# fpga_headers.net
KiCad netlist of a schematic drawn in Altium Designer
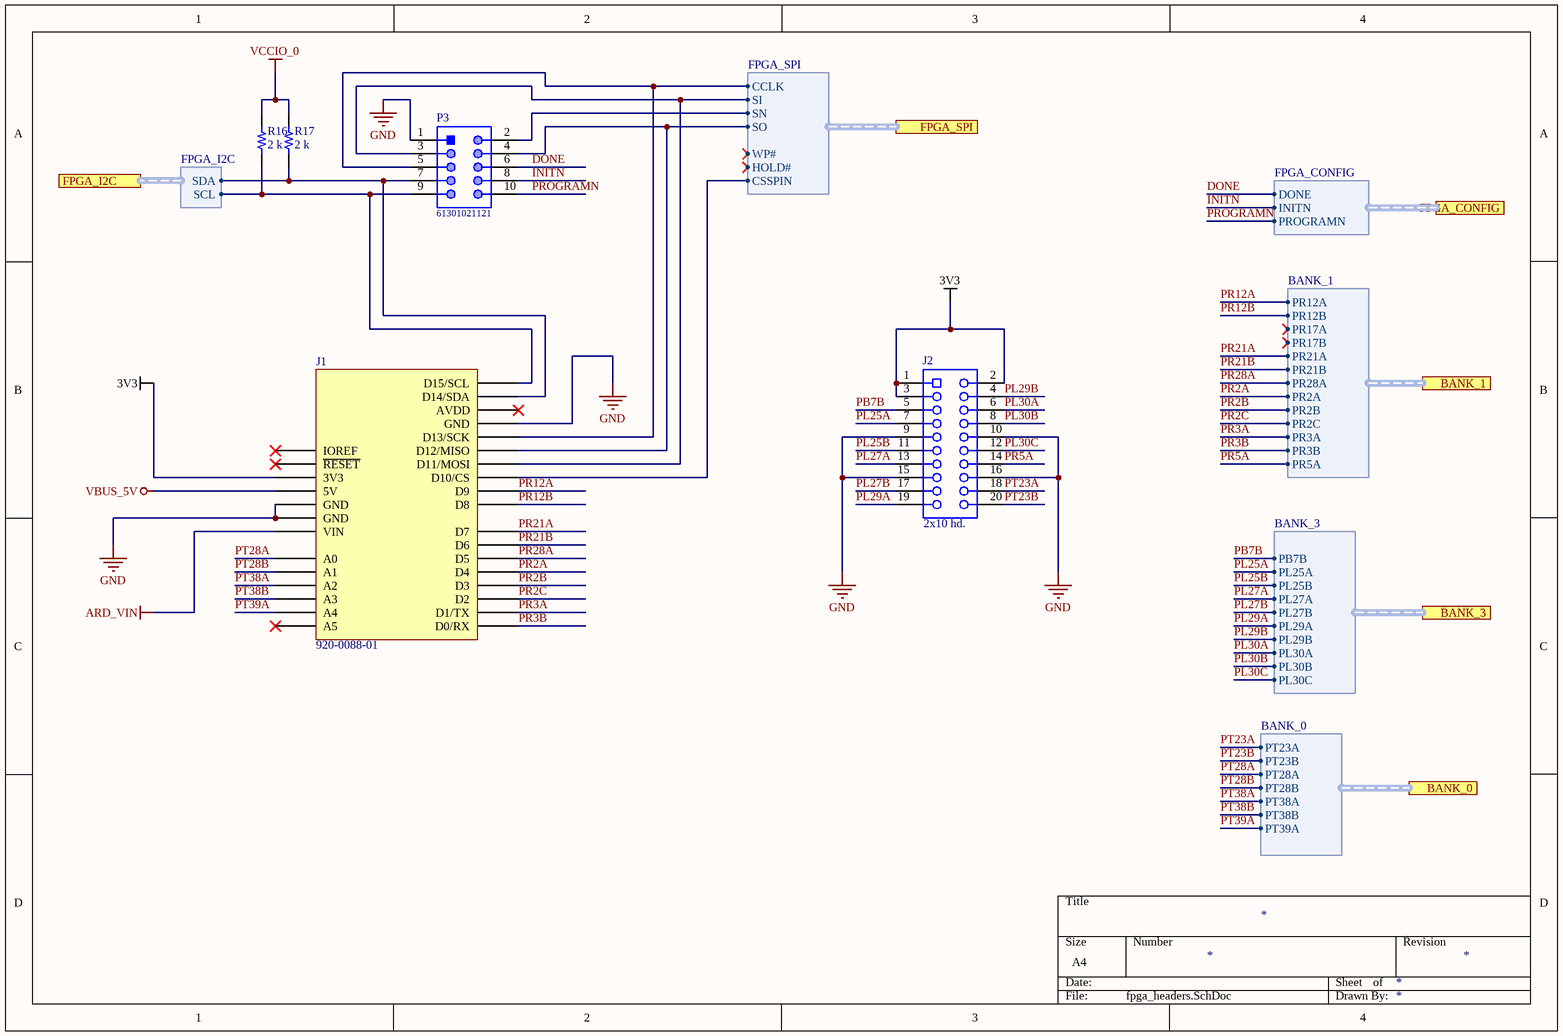
[diagram p0: fpga_headers.SchDoc]

(export (version "E")
  (design (tool "Eeschema 10.0.6"))
  (components
    (comp (ref "J1")
      (value "920-0088-01")
      (footprint "SCHMARTBOARD - 920-0088-01")
      (description "CONN HDR 8/10P 0.1 GOLD PCB 6PC")
      (fields (field (name "MANUFACTURER") "Schmartboard, Inc."))
      (libsource (lib "Celestial Altium Library - altium_library (2)") (part "Arduino Headers"))
    )
    (comp (ref "J2")
      (value "2x10 hd.")
      (footprint "SLIN-PPPC102LFBN-RC_V")
      (libsource (lib "Altium Content Vault") (part "CN-2P-F-R20"))
    )
    (comp (ref "P3")
      (value "61301021121")
      (footprint "61301021121")
      (description "THT Vertical Pin Header WR-PHD, Pitch 2.54 mm, Dual Row, 10 pins")
      (fields (field (name "MANUFACTURER") "Wurth Elektronik") (field (name "PUBLISHER") "WurthElektronik"))
      (libsource (lib "Altium Content Vault") (part "WE-CN-2P-M-R10"))
    )
    (comp (ref "R16")
      (value "2 k")
      (footprint "RES 0603_1608")
      (description "RES 2K OHM 5% 1/10W 0603")
      (fields
        (field (name "PART NUMBER") "RMCF0603JT2K00")
        (field (name "MANUFACTURER") "Stackpole Electronics Inc")
      )
      (libsource (lib "Celestial Altium Library - altium_library (2)") (part "Resistor"))
    )
    (comp (ref "R17")
      (value "2 k")
      (footprint "RES 0603_1608")
      (description "RES 2K OHM 5% 1/10W 0603")
      (fields
        (field (name "PART NUMBER") "RMCF0603JT2K00")
        (field (name "MANUFACTURER") "Stackpole Electronics Inc")
      )
      (libsource (lib "Celestial Altium Library - altium_library (2)") (part "Resistor"))
    )
  )
  (nets
    (net (code "7") (name "/CCLK") (class "Default")
      (node (ref "J1") (pin "28") (pinfunction "D13/SCK_28") (pintype "passive"))
      (node (ref "P3") (pin "5") (pinfunction "5_5") (pintype "passive"))
    )
    (net (code "8") (name "/CSSPIN") (class "Default")
      (node (ref "J1") (pin "25") (pinfunction "D10/CS_25") (pintype "passive"))
    )
    (net (code "9") (name "/DONE") (class "Default")
      (node (ref "P3") (pin "6") (pinfunction "6_6") (pintype "passive"))
    )
    (net (code "10") (name "/INITN") (class "Default")
      (node (ref "P3") (pin "8") (pinfunction "8_8") (pintype "passive"))
    )
    (net (code "11") (name "/PB7B") (class "Default")
      (node (ref "J2") (pin "5") (pinfunction "5_5") (pintype "passive"))
    )
    (net (code "12") (name "/PL25A") (class "Default")
      (node (ref "J2") (pin "7") (pinfunction "7_7") (pintype "passive"))
    )
    (net (code "13") (name "/PL25B") (class "Default")
      (node (ref "J2") (pin "11") (pinfunction "11_11") (pintype "passive"))
    )
    (net (code "14") (name "/PL27A") (class "Default")
      (node (ref "J2") (pin "13") (pinfunction "13_13") (pintype "passive"))
    )
    (net (code "15") (name "/PL27B") (class "Default")
      (node (ref "J2") (pin "17") (pinfunction "17_17") (pintype "passive"))
    )
    (net (code "16") (name "/PL29A") (class "Default")
      (node (ref "J2") (pin "19") (pinfunction "19_19") (pintype "passive"))
    )
    (net (code "17") (name "/PL29B") (class "Default")
      (node (ref "J2") (pin "4") (pinfunction "4_4") (pintype "passive"))
    )
    (net (code "18") (name "/PL30A") (class "Default")
      (node (ref "J2") (pin "6") (pinfunction "6_6") (pintype "passive"))
    )
    (net (code "19") (name "/PL30B") (class "Default")
      (node (ref "J2") (pin "8") (pinfunction "8_8") (pintype "passive"))
    )
    (net (code "20") (name "/PL30C") (class "Default")
      (node (ref "J2") (pin "12") (pinfunction "12_12") (pintype "passive"))
    )
    (net (code "21") (name "/PR2A") (class "Default")
      (node (ref "J1") (pin "19") (pinfunction "D4_19") (pintype "passive"))
    )
    (net (code "22") (name "/PR2B") (class "Default")
      (node (ref "J1") (pin "18") (pinfunction "D3_18") (pintype "passive"))
    )
    (net (code "23") (name "/PR2C") (class "Default")
      (node (ref "J1") (pin "17") (pinfunction "D2_17") (pintype "passive"))
    )
    (net (code "24") (name "/PR3A") (class "Default")
      (node (ref "J1") (pin "16") (pinfunction "D1/TX_16") (pintype "passive"))
    )
    (net (code "25") (name "/PR3B") (class "Default")
      (node (ref "J1") (pin "15") (pinfunction "D0/RX_15") (pintype "passive"))
    )
    (net (code "26") (name "/PR5A") (class "Default")
      (node (ref "J2") (pin "14") (pinfunction "14_14") (pintype "passive"))
    )
    (net (code "27") (name "/PR12A") (class "Default")
      (node (ref "J1") (pin "24") (pinfunction "D9_24") (pintype "passive"))
    )
    (net (code "28") (name "/PR12B") (class "Default")
      (node (ref "J1") (pin "23") (pinfunction "D8_23") (pintype "passive"))
    )
    (net (code "29") (name "/PR21A") (class "Default")
      (node (ref "J1") (pin "22") (pinfunction "D7_22") (pintype "passive"))
    )
    (net (code "30") (name "/PR21B") (class "Default")
      (node (ref "J1") (pin "21") (pinfunction "D6_21") (pintype "passive"))
    )
    (net (code "31") (name "/PR28A") (class "Default")
      (node (ref "J1") (pin "20") (pinfunction "D5_20") (pintype "passive"))
    )
    (net (code "32") (name "/PROGRAMN") (class "Default")
      (node (ref "P3") (pin "10") (pinfunction "10_10") (pintype "passive"))
    )
    (net (code "33") (name "/PT23A") (class "Default")
      (node (ref "J2") (pin "18") (pinfunction "18_18") (pintype "passive"))
    )
    (net (code "34") (name "/PT23B") (class "Default")
      (node (ref "J2") (pin "20") (pinfunction "20_20") (pintype "passive"))
    )
    (net (code "35") (name "/PT28A") (class "Default")
      (node (ref "J1") (pin "9") (pinfunction "A0_9") (pintype "passive"))
    )
    (net (code "36") (name "/PT28B") (class "Default")
      (node (ref "J1") (pin "10") (pinfunction "A1_10") (pintype "passive"))
    )
    (net (code "37") (name "/PT38A") (class "Default")
      (node (ref "J1") (pin "11") (pinfunction "A2_11") (pintype "passive"))
    )
    (net (code "38") (name "/PT38B") (class "Default")
      (node (ref "J1") (pin "12") (pinfunction "A3_12") (pintype "passive"))
    )
    (net (code "39") (name "/PT39A") (class "Default")
      (node (ref "J1") (pin "13") (pinfunction "A4_13") (pintype "passive"))
    )
    (net (code "40") (name "/SCL") (class "Default")
      (node (ref "J1") (pin "32") (pinfunction "D15/SCL_32") (pintype "passive"))
      (node (ref "P3") (pin "9") (pinfunction "9_9") (pintype "passive"))
      (node (ref "R16") (pin "1") (pinfunction "1_1") (pintype "passive"))
    )
    (net (code "41") (name "/SDA") (class "Default")
      (node (ref "J1") (pin "31") (pinfunction "D14/SDA_31") (pintype "passive"))
      (node (ref "P3") (pin "7") (pinfunction "7_7") (pintype "passive"))
      (node (ref "R17") (pin "1") (pinfunction "1_1") (pintype "passive"))
    )
    (net (code "42") (name "/SI") (class "Default")
      (node (ref "J1") (pin "26") (pinfunction "D11/MOSI_26") (pintype "passive"))
      (node (ref "P3") (pin "3") (pinfunction "3_3") (pintype "passive"))
    )
    (net (code "43") (name "/SN") (class "Default")
      (node (ref "P3") (pin "2") (pinfunction "2_2") (pintype "passive"))
    )
    (net (code "44") (name "/SO") (class "Default")
      (node (ref "J1") (pin "27") (pinfunction "D12/MISO_27") (pintype "passive"))
      (node (ref "P3") (pin "4") (pinfunction "4_4") (pintype "passive"))
    )
    (net (code "51") (name "3V3") (class "Default")
      (node (ref "J1") (pin "4") (pinfunction "3V3_4") (pintype "passive"))
      (node (ref "J2") (pin "1") (pinfunction "1_1") (pintype "passive"))
      (node (ref "J2") (pin "2") (pinfunction "2_2") (pintype "passive"))
      (node (ref "J2") (pin "3") (pinfunction "3_3") (pintype "passive"))
    )
    (net (code "52") (name "ARD_VIN") (class "Default")
      (node (ref "J1") (pin "8") (pinfunction "VIN_8") (pintype "passive"))
    )
    (net (code "53") (name "GND") (class "Default")
      (node (ref "J1") (pin "29") (pinfunction "GND_29") (pintype "passive"))
      (node (ref "J1") (pin "6") (pinfunction "GND_6") (pintype "passive"))
      (node (ref "J1") (pin "7") (pinfunction "GND_7") (pintype "passive"))
      (node (ref "J2") (pin "10") (pinfunction "10_10") (pintype "passive"))
      (node (ref "J2") (pin "15") (pinfunction "15_15") (pintype "passive"))
      (node (ref "J2") (pin "16") (pinfunction "16_16") (pintype "passive"))
      (node (ref "J2") (pin "9") (pinfunction "9_9") (pintype "passive"))
      (node (ref "P3") (pin "1") (pinfunction "1_1") (pintype "passive"))
    )
    (net (code "54") (name "VBUS_5V") (class "Default")
      (node (ref "J1") (pin "5") (pinfunction "5V_5") (pintype "passive"))
    )
    (net (code "55") (name "VCCIO_0") (class "Default")
      (node (ref "R16") (pin "2") (pinfunction "2_2") (pintype "passive"))
      (node (ref "R17") (pin "2") (pinfunction "2_2") (pintype "passive"))
    )
    (net (code "56") (name "unconnected-(J1-A5-Pad14)") (class "Default")
      (node (ref "J1") (pin "14") (pinfunction "A5_14") (pintype "passive+no_connect"))
    )
    (net (code "57") (name "unconnected-(J1-AVDD-Pad30)") (class "Default")
      (node (ref "J1") (pin "30") (pinfunction "AVDD_30") (pintype "passive+no_connect"))
    )
    (net (code "58") (name "unconnected-(J1-IOREF-Pad2)") (class "Default")
      (node (ref "J1") (pin "2") (pinfunction "IOREF_2") (pintype "passive+no_connect"))
    )
    (net (code "59") (name "unconnected-(J1-~{RESET}-Pad3)") (class "Default")
      (node (ref "J1") (pin "3") (pinfunction "~{RESET}_3") (pintype "passive+no_connect"))
    )
  )
)
